# Controller-Sheet.net
KiCad netlist of a schematic drawn in Altium Designer
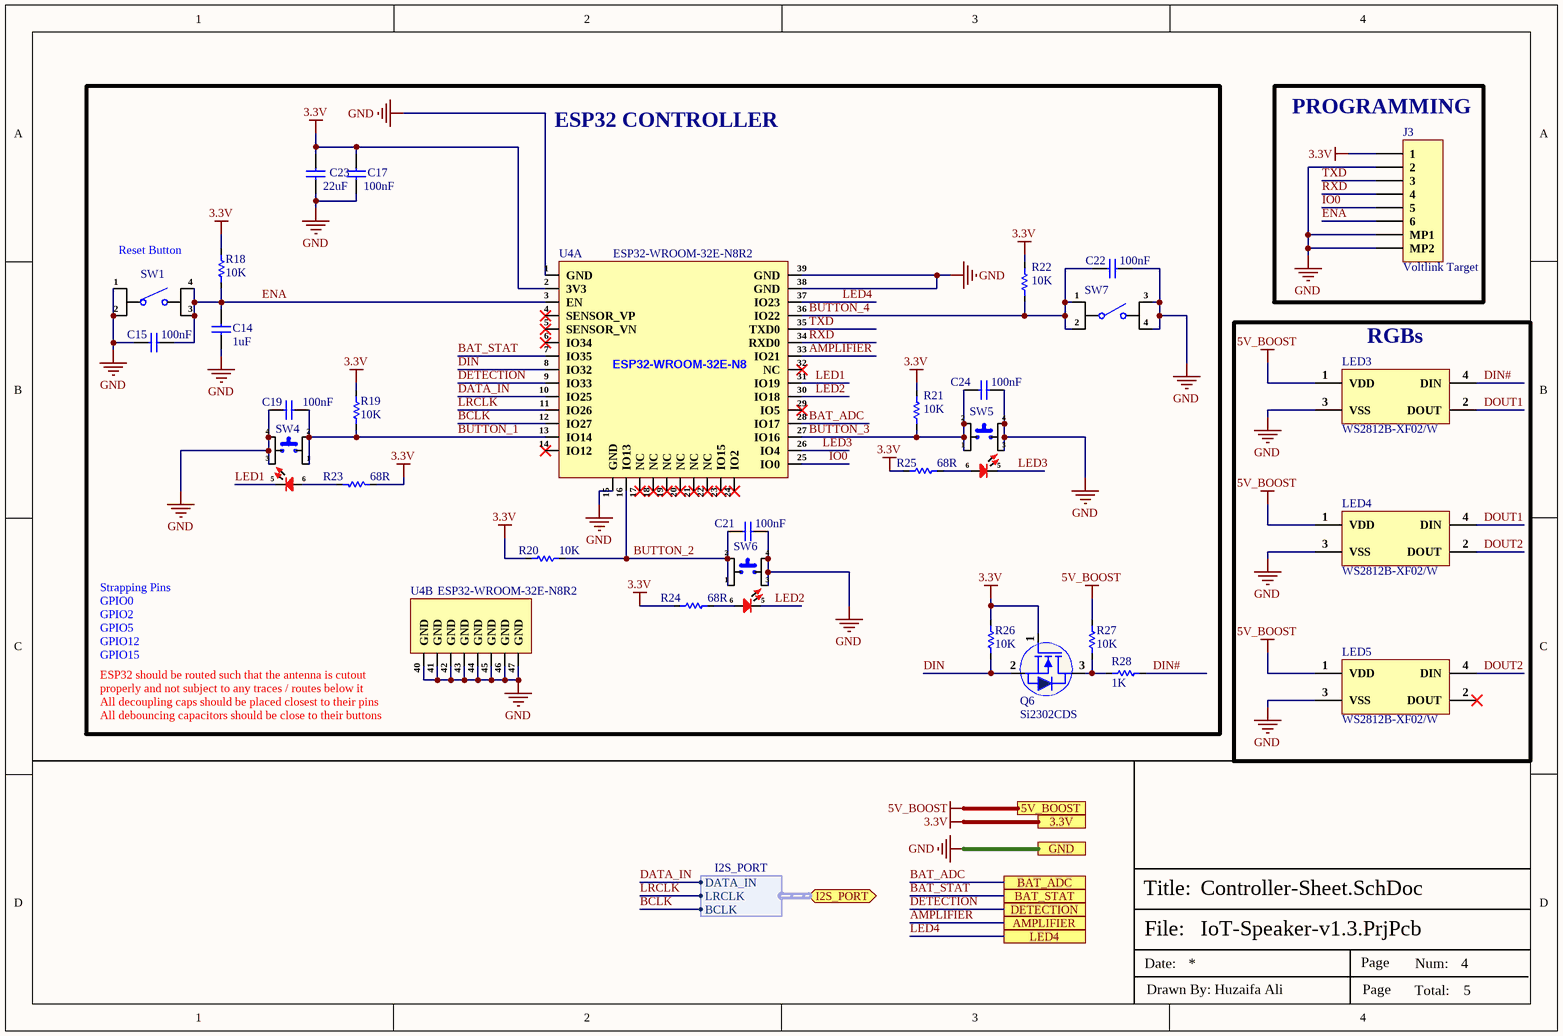
[diagram p0: Controller-Sheet.SchDoc]

(export (version "E")
  (design (tool "Eeschema 10.0.6"))
  (components
    (comp (ref "C14")
      (value "1uF")
      (footprint "Cap-0603")
      (description "CAP CER 1UF 25V X5R 0603")
      (fields
        (field (name "MANUFACTURER") "Yageo")
        (field (name "MANUFACTURER PART NUMBER") "CC0603KRX5R8BB105")
      )
      (libsource (lib "eSpark_centralized_Library(2022)") (part "CC0603KRX5R8BB105"))
    )
    (comp (ref "C15")
      (value "100nF")
      (footprint "Cap-0402")
      (description "CAP CER 0.1UF 25V X5R 0402")
      (fields
        (field (name "MANUFACTURER") "Yageo")
        (field (name "MANUFACTURER PART NUMBER") "CC0402KRX5R8BB104")
      )
      (libsource (lib "eSpark_centralized_Library(2022)") (part "CC0402KRX5R8BB104"))
    )
    (comp (ref "C17")
      (value "100nF")
      (footprint "Cap-0402")
      (description "CAP CER 0.1UF 25V X5R 0402")
      (fields
        (field (name "MANUFACTURER") "Yageo")
        (field (name "MANUFACTURER PART NUMBER") "CC0402KRX5R8BB104")
      )
      (libsource (lib "eSpark_centralized_Library(2022)") (part "CC0402KRX5R8BB104"))
    )
    (comp (ref "C19")
      (value "100nF")
      (footprint "Cap-0402")
      (description "CAP CER 0.1UF 25V X5R 0402")
      (fields
        (field (name "MANUFACTURER") "Yageo")
        (field (name "MANUFACTURER PART NUMBER") "CC0402KRX5R8BB104")
      )
      (libsource (lib "eSpark_centralized_Library(2022)") (part "CC0402KRX5R8BB104"))
    )
    (comp (ref "C21")
      (value "100nF")
      (footprint "Cap-0402")
      (description "CAP CER 0.1UF 25V X5R 0402")
      (fields
        (field (name "MANUFACTURER") "Yageo")
        (field (name "MANUFACTURER PART NUMBER") "CC0402KRX5R8BB104")
      )
      (libsource (lib "eSpark_centralized_Library(2022)") (part "CC0402KRX5R8BB104"))
    )
    (comp (ref "C22")
      (value "100nF")
      (footprint "Cap-0402")
      (description "CAP CER 0.1UF 25V X5R 0402")
      (fields
        (field (name "MANUFACTURER") "Yageo")
        (field (name "MANUFACTURER PART NUMBER") "CC0402KRX5R8BB104")
      )
      (libsource (lib "eSpark_centralized_Library(2022)") (part "CC0402KRX5R8BB104"))
    )
    (comp (ref "C23")
      (value "22uF")
      (footprint "Cap-0603")
      (description "CAP CER 22UF 10V X5R 0603")
      (fields
        (field (name "MANUFACTURER") "Yageo")
        (field (name "MANUFACTURER PART NUMBER") "CC0603MRX5R6BB226")
      )
      (libsource (lib "eSpark_centralized_Library(2022)") (part "CC0603MRX5R6BB226"))
    )
    (comp (ref "C24")
      (value "100nF")
      (footprint "Cap-0402")
      (description "CAP CER 0.1UF 25V X5R 0402")
      (fields
        (field (name "MANUFACTURER") "Yageo")
        (field (name "MANUFACTURER PART NUMBER") "CC0402KRX5R8BB104")
      )
      (libsource (lib "eSpark_centralized_Library(2022)") (part "CC0402KRX5R8BB104"))
    )
    (comp (ref "J3")
      (value "Voltlink Target")
      (footprint "Voltlink Target")
      (description "1x6P SH 1 1mm 6 SMD,P=1mm Wire To Board / Wire To Wire Connector ROHS")
      (fields (field (name "MANUFACTURER") "BOOMELE") (field (name "MANUFACTURER PART NUMBER") "C145963"))
      (libsource (lib "eSpark_centralized_Library(2022)") (part "C145963"))
    )
    (comp (ref "LED3")
      (value "WS2812B-XF02/W")
      (footprint "WS2812B-XF02/W")
      (description "SMD5050 Light Emitting Diodes (LED) ROHS")
      (fields (field (name "MANUFACTURER") "Worldsemi") (field (name "LCSC PART NUMBER") "C4154882"))
      (libsource (lib "eSpark_centralized_Library(2022)") (part "WS2812B-XF02/W"))
    )
    (comp (ref "LED4")
      (value "WS2812B-XF02/W")
      (footprint "WS2812B-XF02/W")
      (description "SMD5050 Light Emitting Diodes (LED) ROHS")
      (fields (field (name "MANUFACTURER") "Worldsemi") (field (name "LCSC PART NUMBER") "C4154882"))
      (libsource (lib "eSpark_centralized_Library(2022)") (part "WS2812B-XF02/W"))
    )
    (comp (ref "LED5")
      (value "WS2812B-XF02/W")
      (footprint "WS2812B-XF02/W")
      (description "SMD5050 Light Emitting Diodes (LED) ROHS")
      (fields (field (name "MANUFACTURER") "Worldsemi") (field (name "LCSC PART NUMBER") "C4154882"))
      (libsource (lib "eSpark_centralized_Library(2022)") (part "WS2812B-XF02/W"))
    )
    (comp (ref "Q6")
      (value "Si2302CDS")
      (footprint "Sot-23")
      (description "N-CHANNEL 20-V (D-S) MOSFET")
      (fields
        (field (name "MANUFACTURER") "TECH PUBLIC")
        (field (name "MANUFACTURER PART NUMBER") "SI2302CDS")
      )
      (libsource (lib "eSpark_centralized_Library(2022)") (part "Si2302CDS"))
    )
    (comp (ref "R18")
      (value "10K")
      (footprint "Res-0603")
      (description "RES SMD 10K Ohm 1% 1/10W 0603")
      (fields
        (field (name "MANUFACTURER") "Yageo")
        (field (name "MANUFACTURER PART NUMBER") "RC0603FR-0710KL")
      )
      (libsource (lib "eSpark_centralized_Library(2022)") (part "RC0603FR-0710KL"))
    )
    (comp (ref "R19")
      (value "10K")
      (footprint "Res-0603")
      (description "RES SMD 10K Ohm 1% 1/10W 0603")
      (fields
        (field (name "MANUFACTURER") "Yageo")
        (field (name "MANUFACTURER PART NUMBER") "RC0603FR-0710KL")
      )
      (libsource (lib "eSpark_centralized_Library(2022)") (part "RC0603FR-0710KL"))
    )
    (comp (ref "R20")
      (value "10K")
      (footprint "Res-0603")
      (description "RES SMD 10K Ohm 1% 1/10W 0603")
      (fields
        (field (name "MANUFACTURER") "Yageo")
        (field (name "MANUFACTURER PART NUMBER") "RC0603FR-0710KL")
      )
      (libsource (lib "eSpark_centralized_Library(2022)") (part "RC0603FR-0710KL"))
    )
    (comp (ref "R21")
      (value "10K")
      (footprint "Res-0603")
      (description "RES SMD 10K Ohm 1% 1/10W 0603")
      (fields
        (field (name "MANUFACTURER") "Yageo")
        (field (name "MANUFACTURER PART NUMBER") "RC0603FR-0710KL")
      )
      (libsource (lib "eSpark_centralized_Library(2022)") (part "RC0603FR-0710KL"))
    )
    (comp (ref "R22")
      (value "10K")
      (footprint "Res-0603")
      (description "RES SMD 10K Ohm 1% 1/10W 0603")
      (fields
        (field (name "MANUFACTURER") "Yageo")
        (field (name "MANUFACTURER PART NUMBER") "RC0603FR-0710KL")
      )
      (libsource (lib "eSpark_centralized_Library(2022)") (part "RC0603FR-0710KL"))
    )
    (comp (ref "R23")
      (value "68R")
      (footprint "Res-0402")
      (description "RES SMD 68 OHM 0.1% 1/16W 0402")
      (fields
        (field (name "MANUFACTURER") "Panasonic")
        (field (name "MANUFACTURER PART NUMBER") "ERA-2AEB680X")
      )
      (libsource (lib "eSpark_centralized_Library(2022)") (part "ERA2AEB680X"))
    )
    (comp (ref "R24")
      (value "68R")
      (footprint "Res-0402")
      (description "RES SMD 68 OHM 0.1% 1/16W 0402")
      (fields
        (field (name "MANUFACTURER") "Panasonic")
        (field (name "MANUFACTURER PART NUMBER") "ERA-2AEB680X")
      )
      (libsource (lib "eSpark_centralized_Library(2022)") (part "ERA2AEB680X"))
    )
    (comp (ref "R25")
      (value "68R")
      (footprint "Res-0402")
      (description "RES SMD 68 OHM 0.1% 1/16W 0402")
      (fields
        (field (name "MANUFACTURER") "Panasonic")
        (field (name "MANUFACTURER PART NUMBER") "ERA-2AEB680X")
      )
      (libsource (lib "eSpark_centralized_Library(2022)") (part "ERA2AEB680X"))
    )
    (comp (ref "R26")
      (value "10K")
      (footprint "Res-0402")
      (description "RES 10K OHM 1% 1/16W 0402")
      (fields
        (field (name "MANUFACTURER") "Yageo")
        (field (name "MANUFACTURER PART NUMBER") "RC0402FR-0710KL")
      )
      (libsource (lib "eSpark_centralized_Library(2022)") (part "RC0402FR-0710KL"))
    )
    (comp (ref "R27")
      (value "10K")
      (footprint "Res-0402")
      (description "RES 10K OHM 1% 1/16W 0402")
      (fields
        (field (name "MANUFACTURER") "Yageo")
        (field (name "MANUFACTURER PART NUMBER") "RC0402FR-0710KL")
      )
      (libsource (lib "eSpark_centralized_Library(2022)") (part "RC0402FR-0710KL"))
    )
    (comp (ref "R28")
      (value "1K")
      (footprint "Res-0603")
      (description "RES SMD 1K OHM 1% 1/10W 0603")
      (fields
        (field (name "MANUFACTURER") "Yageo")
        (field (name "MANUFACTURER PART NUMBER") "RC0603FR-071KL")
      )
      (libsource (lib "eSpark_centralized_Library(2022)") (part "RC0603FR-071KL"))
    )
    (comp (ref "SW1")
      (value "TS-1109S-C-B")
      (footprint "TS-1109S-C-B")
      (fields (field (name "MANUFACTURER") "XKB Connectivity") (field (name "LCSC PART NUMBER") "C381037"))
      (libsource (lib "eSpark_centralized_Library(2022)") (part "TS-1109S-C-B"))
    )
    (comp (ref "SW4")
      (value "TL1260GQRBLK")
      (footprint "TL1260GQRBLK")
      (description "SWITCH TACTILE SPST-NO 0.05A 12V")
      (fields (field (name "MANUFACTURER") "E-Switch"))
      (libsource (lib "eSpark_centralized_Library(2022)") (part "TL1260GQRBLK"))
    )
    (comp (ref "SW5")
      (value "TL1260GQRBLK")
      (footprint "TL1260GQRBLK")
      (description "SWITCH TACTILE SPST-NO 0.05A 12V")
      (fields (field (name "MANUFACTURER") "E-Switch"))
      (libsource (lib "eSpark_centralized_Library(2022)") (part "TL1260GQRBLK"))
    )
    (comp (ref "SW6")
      (value "TL1260GQRBLK")
      (footprint "TL1260GQRBLK")
      (description "SWITCH TACTILE SPST-NO 0.05A 12V")
      (fields (field (name "MANUFACTURER") "E-Switch"))
      (libsource (lib "eSpark_centralized_Library(2022)") (part "TL1260GQRBLK"))
    )
    (comp (ref "SW7")
      (value "TS-1109S-B-J")
      (footprint "TS-1109S-B-J_")
      (fields (field (name "MANUFACTURER") "XKB Connectivity") (field (name "LCSC PART NUMBER") "C480323"))
      (libsource (lib "eSpark_centralized_Library(2022)") (part "TS-1109S-B-J"))
    )
    (comp (ref "U4")
      (value "ESP32-WROOM-32E-N8R2")
      (footprint "38-SMD Module")
      (description "RF TXRX MODULE BT PCB TRACE SMD")
      (fields (field (name "MANUFACTURER") "Espressif Systems") (field (name "LCSC PART NUMBER") "C5361945"))
      (libsource (lib "") (part "ESP32-WROOM-32E-N8R2_1"))
    )
  )
  (nets
    (net (code "2") (name "/AMPLIFIER") (class "Default")
      (node (ref "U4") (pin "33") (pinfunction "IO21_33") (pintype "passive"))
    )
    (net (code "3") (name "/BAT_ADC") (class "Default")
      (node (ref "U4") (pin "28") (pinfunction "IO17_28") (pintype "passive"))
    )
    (net (code "4") (name "/BAT_STAT") (class "Default")
      (node (ref "U4") (pin "7") (pinfunction "IO35_7") (pintype "passive"))
    )
    (net (code "5") (name "/BCLK") (class "Default")
      (node (ref "U4") (pin "12") (pinfunction "IO27_12") (pintype "passive"))
    )
    (net (code "6") (name "/BUTTON_1") (class "Default")
      (node (ref "C19") (pin "1") (pinfunction "1_1") (pintype "passive"))
      (node (ref "R19") (pin "1") (pinfunction "1_1") (pintype "passive"))
      (node (ref "SW4") (pin "1") (pinfunction "1_1") (pintype "passive"))
      (node (ref "SW4") (pin "2") (pinfunction "2_2") (pintype "passive"))
      (node (ref "U4") (pin "13") (pinfunction "IO14_13") (pintype "passive"))
    )
    (net (code "7") (name "/BUTTON_2") (class "Default")
      (node (ref "C21") (pin "1") (pinfunction "1_1") (pintype "passive"))
      (node (ref "R20") (pin "1") (pinfunction "1_1") (pintype "passive"))
      (node (ref "SW6") (pin "1") (pinfunction "1_1") (pintype "passive"))
      (node (ref "SW6") (pin "2") (pinfunction "2_2") (pintype "passive"))
      (node (ref "U4") (pin "16") (pinfunction "IO13_16") (pintype "passive"))
    )
    (net (code "8") (name "/BUTTON_3") (class "Default")
      (node (ref "C24") (pin "1") (pinfunction "1_1") (pintype "passive"))
      (node (ref "R21") (pin "1") (pinfunction "1_1") (pintype "passive"))
      (node (ref "SW5") (pin "1") (pinfunction "1_1") (pintype "passive"))
      (node (ref "SW5") (pin "2") (pinfunction "2_2") (pintype "passive"))
      (node (ref "U4") (pin "27") (pinfunction "IO16_27") (pintype "passive"))
    )
    (net (code "9") (name "/BUTTON_4") (class "Default")
      (node (ref "C22") (pin "1") (pinfunction "1_1") (pintype "passive"))
      (node (ref "R22") (pin "1") (pinfunction "1_1") (pintype "passive"))
      (node (ref "SW7") (pin "1") (pinfunction "1_1") (pintype "passive"))
      (node (ref "SW7") (pin "2") (pinfunction "2_2") (pintype "passive"))
      (node (ref "U4") (pin "36") (pinfunction "IO22_36") (pintype "passive"))
    )
    (net (code "10") (name "/DATA_IN") (class "Default")
      (node (ref "U4") (pin "10") (pinfunction "IO25_10") (pintype "passive"))
    )
    (net (code "11") (name "/DETECTION") (class "Default")
      (node (ref "U4") (pin "9") (pinfunction "IO33_9") (pintype "passive"))
    )
    (net (code "12") (name "/DIN") (class "Default")
      (node (ref "Q6") (pin "2") (pinfunction "S_2") (pintype "passive"))
      (node (ref "R26") (pin "2") (pinfunction "2_2") (pintype "passive"))
      (node (ref "U4") (pin "8") (pinfunction "IO32_8") (pintype "passive"))
    )
    (net (code "13") (name "/DIN#") (class "Default")
      (node (ref "LED3") (pin "4") (pinfunction "DIN_4") (pintype "passive"))
      (node (ref "R28") (pin "2") (pinfunction "2_2") (pintype "passive"))
    )
    (net (code "14") (name "/DOUT1") (class "Default")
      (node (ref "LED3") (pin "2") (pinfunction "DOUT_2") (pintype "passive"))
      (node (ref "LED4") (pin "4") (pinfunction "DIN_4") (pintype "passive"))
    )
    (net (code "15") (name "/DOUT2") (class "Default")
      (node (ref "LED4") (pin "2") (pinfunction "DOUT_2") (pintype "passive"))
      (node (ref "LED5") (pin "4") (pinfunction "DIN_4") (pintype "passive"))
    )
    (net (code "16") (name "/ENA") (class "Default")
      (node (ref "C14") (pin "2") (pinfunction "2_2") (pintype "passive"))
      (node (ref "C15") (pin "2") (pinfunction "2_2") (pintype "passive"))
      (node (ref "J3") (pin "6") (pinfunction "6_6") (pintype "passive"))
      (node (ref "R18") (pin "1") (pinfunction "1_1") (pintype "passive"))
      (node (ref "SW1") (pin "3") (pinfunction "3_3") (pintype "passive"))
      (node (ref "SW1") (pin "4") (pinfunction "4_4") (pintype "passive"))
      (node (ref "U4") (pin "3") (pinfunction "EN_3") (pintype "passive"))
    )
    (net (code "17") (name "/IO0") (class "Default")
      (node (ref "J3") (pin "5") (pinfunction "5_5") (pintype "passive"))
      (node (ref "U4") (pin "25") (pinfunction "IO0_25") (pintype "passive"))
    )
    (net (code "18") (name "/LED1") (class "Default")
      (node (ref "SW4") (pin "5") (pinfunction "-_5") (pintype "passive"))
      (node (ref "U4") (pin "31") (pinfunction "IO19_31") (pintype "passive"))
    )
    (net (code "19") (name "/LED2") (class "Default")
      (node (ref "SW6") (pin "5") (pinfunction "-_5") (pintype "passive"))
      (node (ref "U4") (pin "30") (pinfunction "IO18_30") (pintype "passive"))
    )
    (net (code "20") (name "/LED3") (class "Default")
      (node (ref "SW5") (pin "5") (pinfunction "-_5") (pintype "passive"))
      (node (ref "U4") (pin "26") (pinfunction "IO4_26") (pintype "passive"))
    )
    (net (code "21") (name "/LED4") (class "Default")
      (node (ref "U4") (pin "37") (pinfunction "IO23_37") (pintype "passive"))
    )
    (net (code "22") (name "/LRCLK") (class "Default")
      (node (ref "U4") (pin "11") (pinfunction "IO26_11") (pintype "passive"))
    )
    (net (code "23") (name "/RXD") (class "Default")
      (node (ref "J3") (pin "4") (pinfunction "4_4") (pintype "passive"))
      (node (ref "U4") (pin "34") (pinfunction "RXD0_34") (pintype "passive"))
    )
    (net (code "24") (name "/TXD") (class "Default")
      (node (ref "J3") (pin "3") (pinfunction "3_3") (pintype "passive"))
      (node (ref "U4") (pin "35") (pinfunction "TXD0_35") (pintype "passive"))
    )
    (net (code "26") (name "3.3V") (class "Default")
      (node (ref "C17") (pin "2") (pinfunction "2_2") (pintype "passive"))
      (node (ref "C23") (pin "2") (pinfunction "2_2") (pintype "passive"))
      (node (ref "J3") (pin "1") (pinfunction "1_1") (pintype "passive"))
      (node (ref "Q6") (pin "1") (pinfunction "G_1") (pintype "passive"))
      (node (ref "R18") (pin "2") (pinfunction "2_2") (pintype "passive"))
      (node (ref "R19") (pin "2") (pinfunction "2_2") (pintype "passive"))
      (node (ref "R20") (pin "2") (pinfunction "2_2") (pintype "passive"))
      (node (ref "R21") (pin "2") (pinfunction "2_2") (pintype "passive"))
      (node (ref "R22") (pin "2") (pinfunction "2_2") (pintype "passive"))
      (node (ref "R23") (pin "2") (pinfunction "2_2") (pintype "passive"))
      (node (ref "R24") (pin "2") (pinfunction "2_2") (pintype "passive"))
      (node (ref "R25") (pin "2") (pinfunction "2_2") (pintype "passive"))
      (node (ref "R26") (pin "1") (pinfunction "1_1") (pintype "passive"))
      (node (ref "U4") (pin "2") (pinfunction "3V3_2") (pintype "passive"))
    )
    (net (code "27") (name "5V_BOOST") (class "Default")
      (node (ref "LED3") (pin "1") (pinfunction "VDD_1") (pintype "passive"))
      (node (ref "LED4") (pin "1") (pinfunction "VDD_1") (pintype "passive"))
      (node (ref "LED5") (pin "1") (pinfunction "VDD_1") (pintype "passive"))
      (node (ref "R27") (pin "1") (pinfunction "1_1") (pintype "passive"))
    )
    (net (code "28") (name "GND") (class "Default")
      (node (ref "C14") (pin "1") (pinfunction "1_1") (pintype "passive"))
      (node (ref "C15") (pin "1") (pinfunction "1_1") (pintype "passive"))
      (node (ref "C17") (pin "1") (pinfunction "1_1") (pintype "passive"))
      (node (ref "C19") (pin "2") (pinfunction "2_2") (pintype "passive"))
      (node (ref "C21") (pin "2") (pinfunction "2_2") (pintype "passive"))
      (node (ref "C22") (pin "2") (pinfunction "2_2") (pintype "passive"))
      (node (ref "C23") (pin "1") (pinfunction "1_1") (pintype "passive"))
      (node (ref "C24") (pin "2") (pinfunction "2_2") (pintype "passive"))
      (node (ref "J3") (pin "2") (pinfunction "2_2") (pintype "passive"))
      (node (ref "J3") (pin "MP1") (pinfunction "MP1_MP1") (pintype "passive"))
      (node (ref "J3") (pin "MP2") (pinfunction "MP2_MP2") (pintype "passive"))
      (node (ref "LED3") (pin "3") (pinfunction "VSS_3") (pintype "passive"))
      (node (ref "LED4") (pin "3") (pinfunction "VSS_3") (pintype "passive"))
      (node (ref "LED5") (pin "3") (pinfunction "VSS_3") (pintype "passive"))
      (node (ref "SW1") (pin "1") (pinfunction "1_1") (pintype "passive"))
      (node (ref "SW1") (pin "2") (pinfunction "2_2") (pintype "passive"))
      (node (ref "SW4") (pin "3") (pinfunction "3_3") (pintype "passive"))
      (node (ref "SW4") (pin "4") (pinfunction "4_4") (pintype "passive"))
      (node (ref "SW5") (pin "3") (pinfunction "3_3") (pintype "passive"))
      (node (ref "SW5") (pin "4") (pinfunction "4_4") (pintype "passive"))
      (node (ref "SW6") (pin "3") (pinfunction "3_3") (pintype "passive"))
      (node (ref "SW6") (pin "4") (pinfunction "4_4") (pintype "passive"))
      (node (ref "SW7") (pin "3") (pinfunction "3_3") (pintype "passive"))
      (node (ref "SW7") (pin "4") (pinfunction "4_4") (pintype "passive"))
      (node (ref "U4") (pin "1") (pinfunction "GND_1") (pintype "passive"))
      (node (ref "U4") (pin "15") (pinfunction "GND_15") (pintype "passive"))
      (node (ref "U4") (pin "38") (pinfunction "GND_38") (pintype "passive"))
      (node (ref "U4") (pin "39") (pinfunction "GND_39") (pintype "passive"))
      (node (ref "U4") (pin "40") (pinfunction "GND_40") (pintype "passive"))
      (node (ref "U4") (pin "41") (pinfunction "GND_41") (pintype "passive"))
      (node (ref "U4") (pin "42") (pinfunction "GND_42") (pintype "passive"))
      (node (ref "U4") (pin "43") (pinfunction "GND_43") (pintype "passive"))
      (node (ref "U4") (pin "44") (pinfunction "GND_44") (pintype "passive"))
      (node (ref "U4") (pin "45") (pinfunction "GND_45") (pintype "passive"))
      (node (ref "U4") (pin "46") (pinfunction "GND_46") (pintype "passive"))
      (node (ref "U4") (pin "47") (pinfunction "GND_47") (pintype "passive"))
    )
    (net (code "29") (name "Net-(Q6-D)") (class "Default")
      (node (ref "Q6") (pin "3") (pinfunction "D_3") (pintype "passive"))
      (node (ref "R27") (pin "2") (pinfunction "2_2") (pintype "passive"))
      (node (ref "R28") (pin "1") (pinfunction "1_1") (pintype "passive"))
    )
    (net (code "30") (name "Net-(SW4-+)") (class "Default")
      (node (ref "R23") (pin "1") (pinfunction "1_1") (pintype "passive"))
      (node (ref "SW4") (pin "6") (pinfunction "+_6") (pintype "passive"))
    )
    (net (code "31") (name "Net-(SW5-+)") (class "Default")
      (node (ref "R25") (pin "1") (pinfunction "1_1") (pintype "passive"))
      (node (ref "SW5") (pin "6") (pinfunction "+_6") (pintype "passive"))
    )
    (net (code "32") (name "Net-(SW6-+)") (class "Default")
      (node (ref "R24") (pin "1") (pinfunction "1_1") (pintype "passive"))
      (node (ref "SW6") (pin "6") (pinfunction "+_6") (pintype "passive"))
    )
    (net (code "33") (name "unconnected-(LED5-DOUT-Pad2)") (class "Default")
      (node (ref "LED5") (pin "2") (pinfunction "DOUT_2") (pintype "passive+no_connect"))
    )
    (net (code "34") (name "unconnected-(U4A-IO2-Pad24)") (class "Default")
      (node (ref "U4") (pin "24") (pinfunction "IO2_24") (pintype "passive+no_connect"))
    )
    (net (code "35") (name "unconnected-(U4A-IO5-Pad29)") (class "Default")
      (node (ref "U4") (pin "29") (pinfunction "IO5_29") (pintype "passive+no_connect"))
    )
    (net (code "36") (name "unconnected-(U4A-IO12-Pad14)") (class "Default")
      (node (ref "U4") (pin "14") (pinfunction "IO12_14") (pintype "passive+no_connect"))
    )
    (net (code "37") (name "unconnected-(U4A-IO15-Pad23)") (class "Default")
      (node (ref "U4") (pin "23") (pinfunction "IO15_23") (pintype "passive+no_connect"))
    )
    (net (code "38") (name "unconnected-(U4A-IO34-Pad6)") (class "Default")
      (node (ref "U4") (pin "6") (pinfunction "IO34_6") (pintype "passive+no_connect"))
    )
    (net (code "39") (name "unconnected-(U4A-NC-Pad17)") (class "Default")
      (node (ref "U4") (pin "17") (pinfunction "NC_17") (pintype "passive+no_connect"))
    )
    (net (code "40") (name "unconnected-(U4A-NC-Pad18)") (class "Default")
      (node (ref "U4") (pin "18") (pinfunction "NC_18") (pintype "passive+no_connect"))
    )
    (net (code "41") (name "unconnected-(U4A-NC-Pad19)") (class "Default")
      (node (ref "U4") (pin "19") (pinfunction "NC_19") (pintype "passive+no_connect"))
    )
    (net (code "42") (name "unconnected-(U4A-NC-Pad20)") (class "Default")
      (node (ref "U4") (pin "20") (pinfunction "NC_20") (pintype "passive+no_connect"))
    )
    (net (code "43") (name "unconnected-(U4A-NC-Pad21)") (class "Default")
      (node (ref "U4") (pin "21") (pinfunction "NC_21") (pintype "passive+no_connect"))
    )
    (net (code "44") (name "unconnected-(U4A-NC-Pad22)") (class "Default")
      (node (ref "U4") (pin "22") (pinfunction "NC_22") (pintype "passive+no_connect"))
    )
    (net (code "45") (name "unconnected-(U4A-NC-Pad32)") (class "Default")
      (node (ref "U4") (pin "32") (pinfunction "NC_32") (pintype "passive+no_connect"))
    )
    (net (code "46") (name "unconnected-(U4A-SENSOR_VN-Pad5)") (class "Default")
      (node (ref "U4") (pin "5") (pinfunction "SENSOR_VN_5") (pintype "passive+no_connect"))
    )
    (net (code "47") (name "unconnected-(U4A-SENSOR_VP-Pad4)") (class "Default")
      (node (ref "U4") (pin "4") (pinfunction "SENSOR_VP_4") (pintype "passive+no_connect"))
    )
  )
)
